# sch.net
KiCad netlist of a schematic drawn in Altium Designer
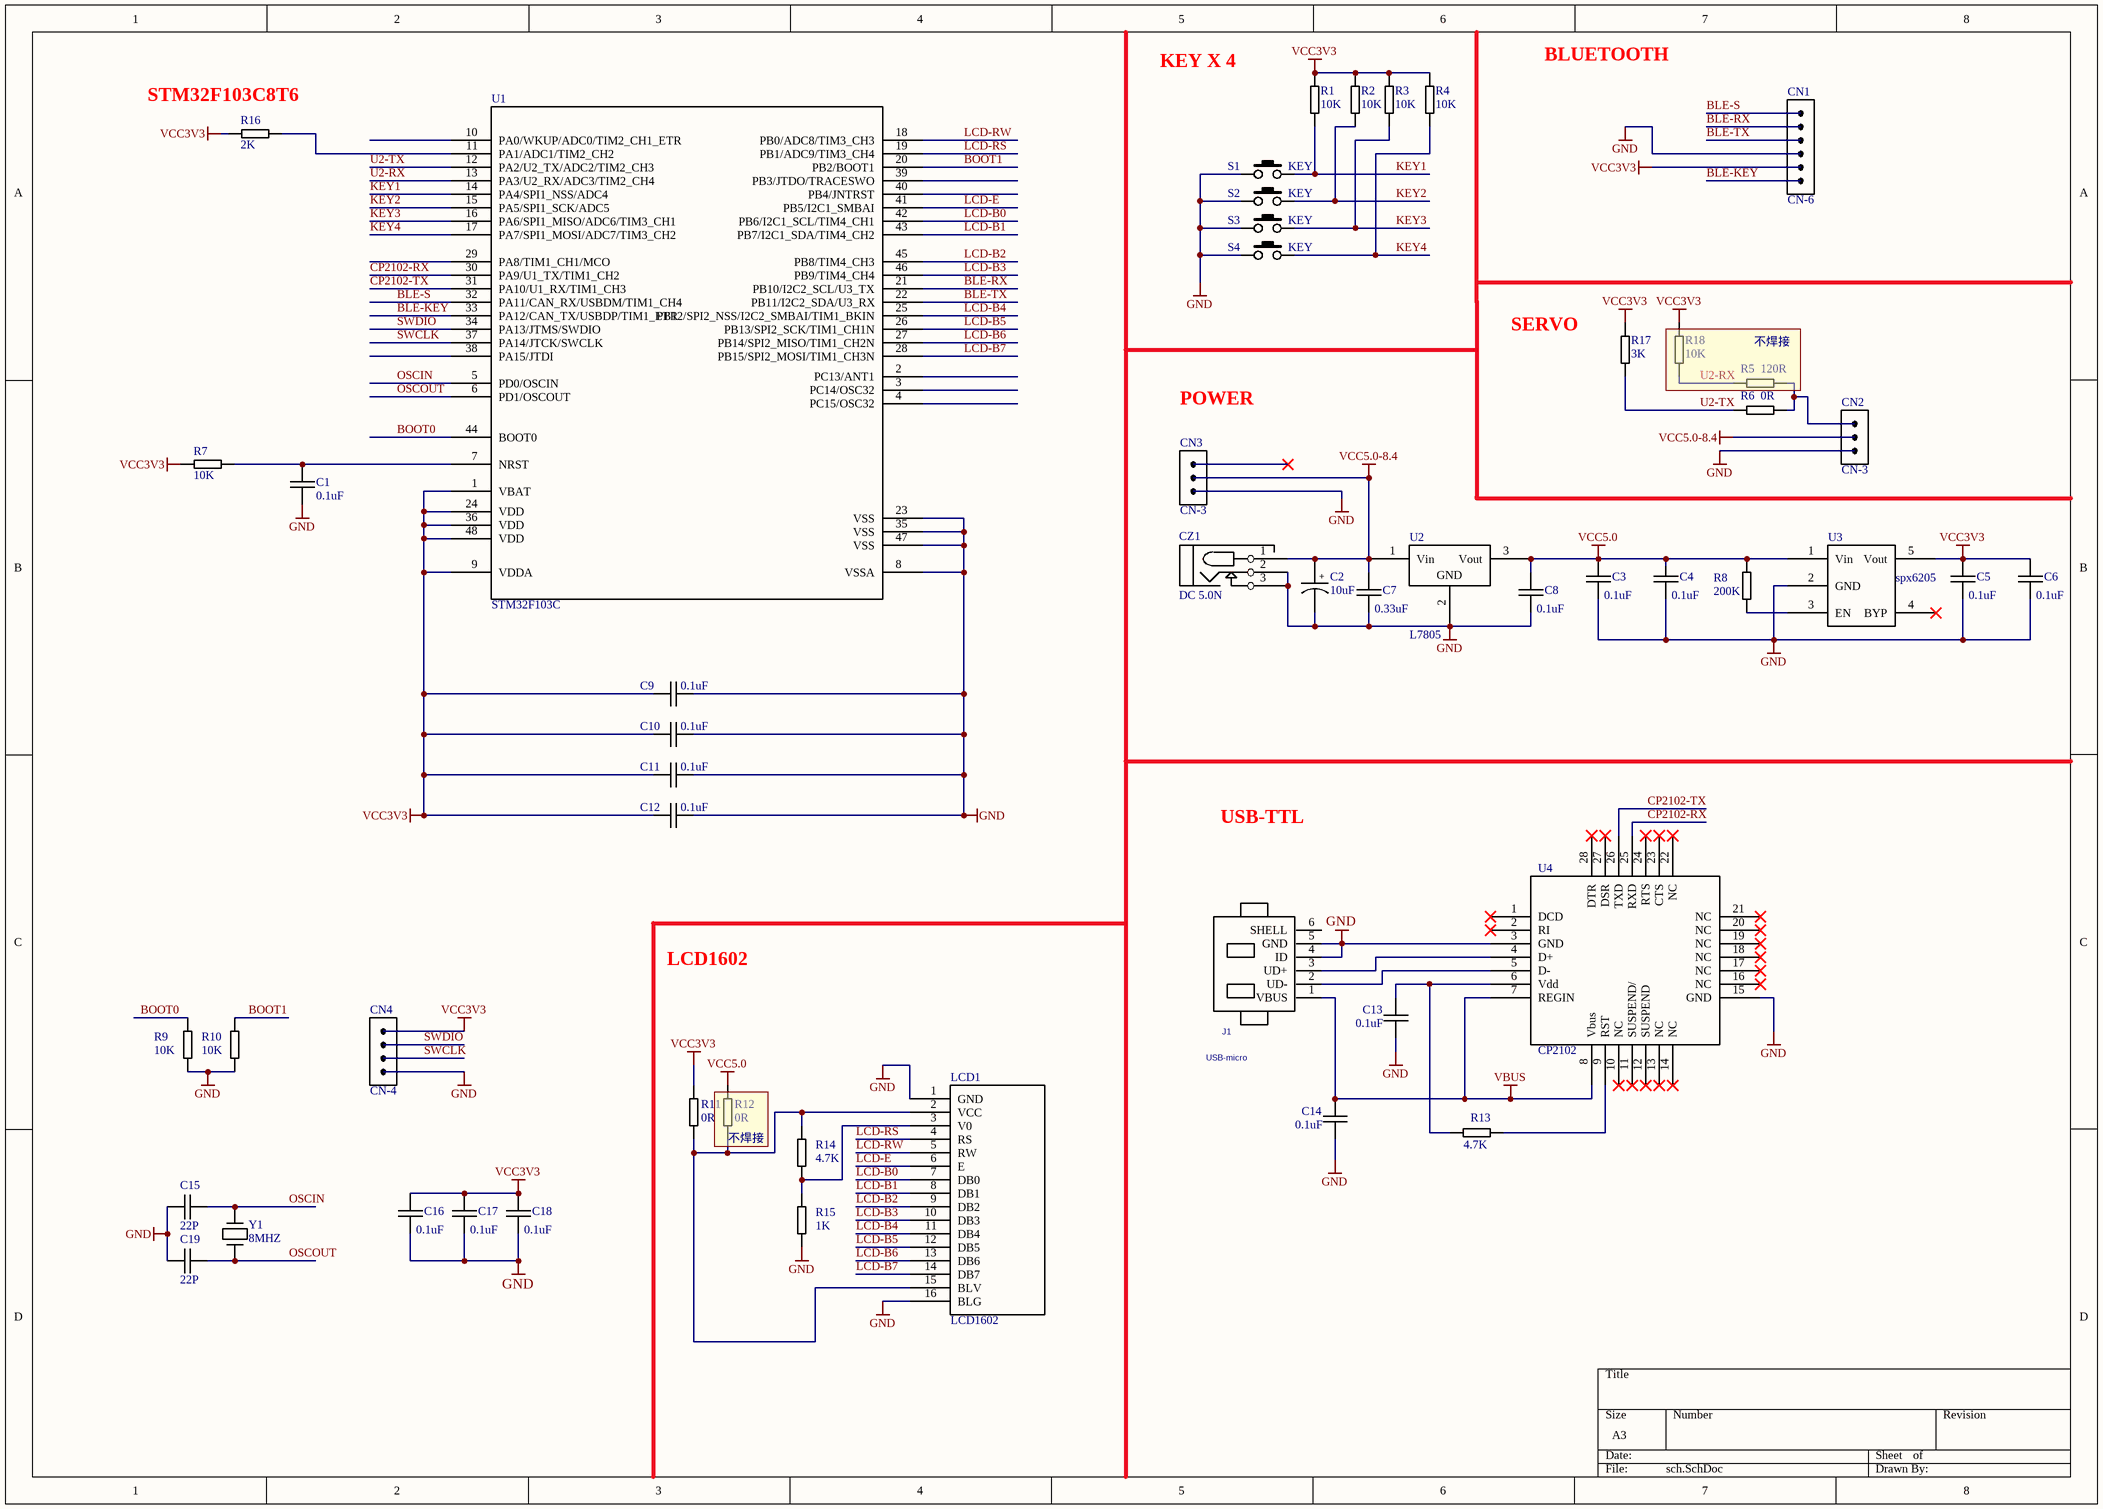
[diagram p0: sch.SchDoc]

(export (version "E")
  (design (tool "Eeschema 10.0.6"))
  (components
    (comp (ref "C1")
      (value "0.1uF")
      (footprint "CAP-0603")
      (description "Capacitor")
      (libsource (lib "综合元件") (part "CAP"))
    )
    (comp (ref "C2")
      (value "10uF")
      (footprint "CAP-A")
      (description "Polar Capacitor")
      (libsource (lib "1-Components") (part "CAP(POL)"))
    )
    (comp (ref "C3")
      (value "0.1uF")
      (footprint "CAP-0603")
      (description "Capacitor")
      (libsource (lib "综合元件") (part "CAP"))
    )
    (comp (ref "C4")
      (value "0.1uF")
      (footprint "CAP-0603")
      (description "Capacitor")
      (libsource (lib "综合元件") (part "CAP"))
    )
    (comp (ref "C5")
      (value "0.1uF")
      (footprint "CAP-0603")
      (description "Capacitor")
      (libsource (lib "综合元件") (part "CAP"))
    )
    (comp (ref "C6")
      (value "0.1uF")
      (footprint "CAP-0603")
      (description "Capacitor")
      (libsource (lib "综合元件") (part "CAP"))
    )
    (comp (ref "C7")
      (value "0.33uF")
      (footprint "CAP-0603")
      (description "Capacitor")
      (libsource (lib "综合元件") (part "CAP"))
    )
    (comp (ref "C8")
      (value "0.1uF")
      (footprint "CAP-0603")
      (description "Capacitor")
      (libsource (lib "综合元件") (part "CAP"))
    )
    (comp (ref "C9")
      (value "0.1uF")
      (footprint "CAP-0603")
      (description "Capacitor")
      (libsource (lib "综合元件") (part "CAP"))
    )
    (comp (ref "C10")
      (value "0.1uF")
      (footprint "CAP-0603")
      (description "Capacitor")
      (libsource (lib "综合元件") (part "CAP"))
    )
    (comp (ref "C11")
      (value "0.1uF")
      (footprint "CAP-0603")
      (description "Capacitor")
      (libsource (lib "综合元件") (part "CAP"))
    )
    (comp (ref "C12")
      (value "0.1uF")
      (footprint "CAP-0603")
      (description "Capacitor")
      (libsource (lib "综合元件") (part "CAP"))
    )
    (comp (ref "C13")
      (value "0.1uF")
      (footprint "CAP-0603")
      (description "Capacitor")
      (libsource (lib "综合元件") (part "CAP"))
    )
    (comp (ref "C14")
      (value "0.1uF")
      (footprint "CAP-0603")
      (description "Capacitor")
      (libsource (lib "综合元件") (part "CAP"))
    )
    (comp (ref "C15")
      (value "22P")
      (footprint "CAP-0603")
      (description "Capacitor")
      (libsource (lib "1-Components") (part "CAP"))
    )
    (comp (ref "C16")
      (value "0.1uF")
      (footprint "CAP-0603")
      (description "Capacitor")
      (libsource (lib "综合元件") (part "CAP"))
    )
    (comp (ref "C17")
      (value "0.1uF")
      (footprint "CAP-0603")
      (description "Capacitor")
      (libsource (lib "综合元件") (part "CAP"))
    )
    (comp (ref "C18")
      (value "0.1uF")
      (footprint "CAP-0603")
      (description "Capacitor")
      (libsource (lib "综合元件") (part "CAP"))
    )
    (comp (ref "C19")
      (value "22P")
      (footprint "CAP-0603")
      (description "Capacitor")
      (libsource (lib "1-Components") (part "CAP"))
    )
    (comp (ref "CN1") (value "CN-6") (footprint "CN-6") (libsource (lib "2-Connectors") (part "CN-6")))
    (comp (ref "CN2") (value "CN-3") (footprint "IDC-3×1") (libsource (lib "2-Connectors") (part "CN-3")))
    (comp (ref "CN3") (value "CN-3") (footprint "IDC-3×1") (libsource (lib "2-Connectors") (part "CN-3")))
    (comp (ref "CN4") (value "CN-4") (footprint "CN-4") (libsource (lib "2-Connectors") (part "CN-4")))
    (comp (ref "CZ1")
      (value "DC 5.0N")
      (footprint "DC-005(N)")
      (libsource (lib "2-Connectors") (part "DC 5.0N"))
    )
    (comp (ref "J1")
      (value "USB-micro")
      (footprint "USB-MICRO")
      (libsource (lib "2-Connectors") (part "USB-micro"))
    )
    (comp (ref "LCD1")
      (value "LCD1602")
      (footprint "LCD1602")
      (libsource (lib "6-Modulars") (part "LCD1602"))
    )
    (comp (ref "R1")
      (value "10K")
      (footprint "RES-0603")
      (description "Resistor")
      (libsource (lib "1-Components") (part "RES"))
    )
    (comp (ref "R2")
      (value "10K")
      (footprint "RES-0603")
      (description "Resistor")
      (libsource (lib "1-Components") (part "RES"))
    )
    (comp (ref "R3")
      (value "10K")
      (footprint "RES-0603")
      (description "Resistor")
      (libsource (lib "1-Components") (part "RES"))
    )
    (comp (ref "R4")
      (value "10K")
      (footprint "RES-0603")
      (description "Resistor")
      (libsource (lib "1-Components") (part "RES"))
    )
    (comp (ref "R5")
      (value "120R")
      (footprint "RES-0603")
      (description "Resistor")
      (libsource (lib "1-Components") (part "RES"))
    )
    (comp (ref "R6")
      (value "0R")
      (footprint "RES-0603")
      (description "Resistor")
      (libsource (lib "1-Components") (part "RES"))
    )
    (comp (ref "R7")
      (value "10K")
      (footprint "RES-0603")
      (description "Resistor")
      (libsource (lib "综合元件") (part "RES"))
    )
    (comp (ref "R8")
      (value "200K")
      (footprint "RES-0603")
      (description "Resistor")
      (libsource (lib "1-Components") (part "RES"))
    )
    (comp (ref "R9")
      (value "10K")
      (footprint "RES-0603")
      (description "Resistor")
      (libsource (lib "1-Components") (part "RES"))
    )
    (comp (ref "R10")
      (value "10K")
      (footprint "RES-0603")
      (description "Resistor")
      (libsource (lib "1-Components") (part "RES"))
    )
    (comp (ref "R11")
      (value "0R")
      (footprint "RES-0603")
      (description "Resistor")
      (libsource (lib "1-Components") (part "RES"))
    )
    (comp (ref "R12")
      (value "0R")
      (footprint "RES-0603")
      (description "Resistor")
      (libsource (lib "1-Components") (part "RES"))
    )
    (comp (ref "R13")
      (value "4.7K")
      (footprint "RES-0603")
      (description "Resistor")
      (libsource (lib "1-Components") (part "RES"))
    )
    (comp (ref "R14")
      (value "4.7K")
      (footprint "RES-0603")
      (description "Resistor")
      (libsource (lib "1-Components") (part "RES"))
    )
    (comp (ref "R15")
      (value "1K")
      (footprint "RES-0603")
      (description "Resistor")
      (libsource (lib "1-Components") (part "RES"))
    )
    (comp (ref "R16")
      (value "2K")
      (footprint "RES-0603")
      (description "Resistor")
      (libsource (lib "1-Components") (part "RES"))
    )
    (comp (ref "R17")
      (value "3K")
      (footprint "RES-0603")
      (description "Resistor")
      (libsource (lib "1-Components") (part "RES"))
    )
    (comp (ref "R18")
      (value "10K")
      (footprint "RES-0603")
      (description "Resistor")
      (libsource (lib "1-Components") (part "RES"))
    )
    (comp (ref "S1") (value "KEY") (footprint "KEY-6A") (libsource (lib "2-Connectors") (part "KEY")))
    (comp (ref "S2") (value "KEY") (footprint "KEY-6A") (libsource (lib "2-Connectors") (part "KEY")))
    (comp (ref "S3") (value "KEY") (footprint "KEY-6A") (libsource (lib "2-Connectors") (part "KEY")))
    (comp (ref "S4") (value "KEY") (footprint "KEY-6A") (libsource (lib "2-Connectors") (part "KEY")))
    (comp (ref "U1")
      (value "STM32F103C")
      (footprint "LQFP-48")
      (fields (field (name "PUBLISHER") "Altium Limited"))
      (libsource (lib "5-ICs Mcu") (part "STM32F103C(LQFP)"))
    )
    (comp (ref "U2") (value "L7805") (footprint "TO-252") (libsource (lib "3-ICs Normal") (part "78XX")))
    (comp (ref "U3")
      (value "spx6205")
      (footprint "SOT-23(5)")
      (libsource (lib "3-ICs Normal") (part "SP6205(FIXED)"))
    )
    (comp (ref "U4") (value "CP2102") (footprint "QFN-28") (libsource (lib "5-ICs Mcu") (part "MPU6050_1")))
    (comp (ref "Y1")
      (value "8MHZ")
      (footprint "XTAL-2512")
      (description "Crystal")
      (libsource (lib "1-Components") (part "XTAL(1)"))
    )
  )
  (nets
    (net (code "1") (name "/BLE-KEY") (class "Default")
      (node (ref "CN1") (pin "6") (pinfunction "6_6") (pintype "passive"))
      (node (ref "U1") (pin "33") (pinfunction "PA12/CAN_TX/USBDP/TIM1_ETR_33") (pintype "passive"))
    )
    (net (code "2") (name "/BLE-RX") (class "Default")
      (node (ref "CN1") (pin "2") (pinfunction "2_2") (pintype "passive"))
      (node (ref "U1") (pin "21") (pinfunction "PB10/I2C2_SCL/U3_TX_21") (pintype "passive"))
    )
    (net (code "3") (name "/BLE-S") (class "Default")
      (node (ref "CN1") (pin "1") (pinfunction "1_1") (pintype "passive"))
      (node (ref "U1") (pin "32") (pinfunction "PA11/CAN_RX/USBDM/TIM1_CH4_32") (pintype "passive"))
    )
    (net (code "4") (name "/BLE-TX") (class "Default")
      (node (ref "CN1") (pin "3") (pinfunction "3_3") (pintype "passive"))
      (node (ref "U1") (pin "22") (pinfunction "PB11/I2C2_SDA/U3_RX_22") (pintype "passive"))
    )
    (net (code "5") (name "/BOOT0") (class "Default")
      (node (ref "R9") (pin "1") (pinfunction "1_1") (pintype "passive"))
      (node (ref "U1") (pin "44") (pinfunction "BOOT0_44") (pintype "passive"))
    )
    (net (code "6") (name "/BOOT1") (class "Default")
      (node (ref "R10") (pin "1") (pinfunction "1_1") (pintype "passive"))
      (node (ref "U1") (pin "20") (pinfunction "PB2/BOOT1_20") (pintype "passive"))
    )
    (net (code "7") (name "/CP2102-RX") (class "Default")
      (node (ref "U1") (pin "30") (pinfunction "PA9/U1_TX/TIM1_CH2_30") (pintype "passive"))
      (node (ref "U4") (pin "25") (pinfunction "RXD_25") (pintype "passive"))
    )
    (net (code "8") (name "/CP2102-TX") (class "Default")
      (node (ref "U1") (pin "31") (pinfunction "PA10/U1_RX/TIM1_CH3_31") (pintype "passive"))
      (node (ref "U4") (pin "26") (pinfunction "TXD_26") (pintype "passive"))
    )
    (net (code "9") (name "/KEY1") (class "Default")
      (node (ref "R1") (pin "1") (pinfunction "1_1") (pintype "passive"))
      (node (ref "S1") (pin "2") (pinfunction "2_2") (pintype "passive"))
      (node (ref "U1") (pin "14") (pinfunction "PA4/SPI1_NSS/ADC4_14") (pintype "passive"))
    )
    (net (code "10") (name "/KEY2") (class "Default")
      (node (ref "R2") (pin "1") (pinfunction "1_1") (pintype "passive"))
      (node (ref "S2") (pin "2") (pinfunction "2_2") (pintype "passive"))
      (node (ref "U1") (pin "15") (pinfunction "PA5/SPI1_SCK/ADC5_15") (pintype "passive"))
    )
    (net (code "11") (name "/KEY3") (class "Default")
      (node (ref "R3") (pin "1") (pinfunction "1_1") (pintype "passive"))
      (node (ref "S3") (pin "2") (pinfunction "2_2") (pintype "passive"))
      (node (ref "U1") (pin "16") (pinfunction "PA6/SPI1_MISO/ADC6/TIM3_CH1_16") (pintype "passive"))
    )
    (net (code "12") (name "/KEY4") (class "Default")
      (node (ref "R4") (pin "1") (pinfunction "1_1") (pintype "passive"))
      (node (ref "S4") (pin "2") (pinfunction "2_2") (pintype "passive"))
      (node (ref "U1") (pin "17") (pinfunction "PA7/SPI1_MOSI/ADC7/TIM3_CH2_17") (pintype "passive"))
    )
    (net (code "13") (name "/LCD-B0") (class "Default")
      (node (ref "LCD1") (pin "7") (pinfunction "DB0_7") (pintype "passive"))
      (node (ref "U1") (pin "42") (pinfunction "PB6/I2C1_SCL/TIM4_CH1_42") (pintype "passive"))
    )
    (net (code "14") (name "/LCD-B1") (class "Default")
      (node (ref "LCD1") (pin "8") (pinfunction "DB1_8") (pintype "passive"))
      (node (ref "U1") (pin "43") (pinfunction "PB7/I2C1_SDA/TIM4_CH2_43") (pintype "passive"))
    )
    (net (code "15") (name "/LCD-B2") (class "Default")
      (node (ref "LCD1") (pin "9") (pinfunction "DB2_9") (pintype "passive"))
      (node (ref "U1") (pin "45") (pinfunction "PB8/TIM4_CH3_45") (pintype "passive"))
    )
    (net (code "16") (name "/LCD-B3") (class "Default")
      (node (ref "LCD1") (pin "10") (pinfunction "DB3_10") (pintype "passive"))
      (node (ref "U1") (pin "46") (pinfunction "PB9/TIM4_CH4_46") (pintype "passive"))
    )
    (net (code "17") (name "/LCD-B4") (class "Default")
      (node (ref "LCD1") (pin "11") (pinfunction "DB4_11") (pintype "passive"))
      (node (ref "U1") (pin "25") (pinfunction "PB12/SPI2_NSS/I2C2_SMBAI/TIM1_BKIN_25") (pintype "passive"))
    )
    (net (code "18") (name "/LCD-B5") (class "Default")
      (node (ref "LCD1") (pin "12") (pinfunction "DB5_12") (pintype "passive"))
      (node (ref "U1") (pin "26") (pinfunction "PB13/SPI2_SCK/TIM1_CH1N_26") (pintype "passive"))
    )
    (net (code "19") (name "/LCD-B6") (class "Default")
      (node (ref "LCD1") (pin "13") (pinfunction "DB6_13") (pintype "passive"))
      (node (ref "U1") (pin "27") (pinfunction "PB14/SPI2_MISO/TIM1_CH2N_27") (pintype "passive"))
    )
    (net (code "20") (name "/LCD-B7") (class "Default")
      (node (ref "LCD1") (pin "14") (pinfunction "DB7_14") (pintype "passive"))
      (node (ref "U1") (pin "28") (pinfunction "PB15/SPI2_MOSI/TIM1_CH3N_28") (pintype "passive"))
    )
    (net (code "21") (name "/LCD-E") (class "Default")
      (node (ref "LCD1") (pin "6") (pinfunction "E_6") (pintype "passive"))
      (node (ref "U1") (pin "41") (pinfunction "PB5/I2C1_SMBAI_41") (pintype "passive"))
    )
    (net (code "22") (name "/LCD-RS") (class "Default")
      (node (ref "LCD1") (pin "4") (pinfunction "RS_4") (pintype "passive"))
      (node (ref "U1") (pin "19") (pinfunction "PB1/ADC9/TIM3_CH4_19") (pintype "passive"))
    )
    (net (code "23") (name "/LCD-RW") (class "Default")
      (node (ref "LCD1") (pin "5") (pinfunction "RW_5") (pintype "passive"))
      (node (ref "U1") (pin "18") (pinfunction "PB0/ADC8/TIM3_CH3_18") (pintype "passive"))
    )
    (net (code "24") (name "/OSCIN") (class "Default")
      (node (ref "C15") (pin "2") (pinfunction "2_2") (pintype "passive"))
      (node (ref "U1") (pin "5") (pinfunction "PD0/OSCIN_5") (pintype "passive"))
      (node (ref "Y1") (pin "2") (pinfunction "2_2") (pintype "passive"))
    )
    (net (code "25") (name "/OSCOUT") (class "Default")
      (node (ref "C19") (pin "2") (pinfunction "2_2") (pintype "passive"))
      (node (ref "U1") (pin "6") (pinfunction "PD1/OSCOUT_6") (pintype "passive"))
      (node (ref "Y1") (pin "1") (pinfunction "1_1") (pintype "passive"))
    )
    (net (code "26") (name "/SWCLK") (class "Default")
      (node (ref "CN4") (pin "3") (pinfunction "3_3") (pintype "passive"))
      (node (ref "U1") (pin "37") (pinfunction "PA14/JTCK/SWCLK_37") (pintype "passive"))
    )
    (net (code "27") (name "/SWDIO") (class "Default")
      (node (ref "CN4") (pin "2") (pinfunction "2_2") (pintype "passive"))
      (node (ref "U1") (pin "34") (pinfunction "PA13/JTMS/SWDIO_34") (pintype "passive"))
    )
    (net (code "28") (name "/U2-RX") (class "Default")
      (node (ref "R18") (pin "1") (pinfunction "1_1") (pintype "passive"))
      (node (ref "R5") (pin "1") (pinfunction "1_1") (pintype "passive"))
      (node (ref "U1") (pin "13") (pinfunction "PA3/U2_RX/ADC3/TIM2_CH4_13") (pintype "passive"))
    )
    (net (code "29") (name "/U2-TX") (class "Default")
      (node (ref "R17") (pin "1") (pinfunction "1_1") (pintype "passive"))
      (node (ref "R6") (pin "1") (pinfunction "1_1") (pintype "passive"))
      (node (ref "U1") (pin "12") (pinfunction "PA2/U2_TX/ADC2/TIM2_CH3_12") (pintype "passive"))
    )
    (net (code "30") (name "GND") (class "Default")
      (node (ref "C1") (pin "2") (pinfunction "2_2") (pintype "passive"))
      (node (ref "C10") (pin "1") (pinfunction "1_1") (pintype "passive"))
      (node (ref "C11") (pin "1") (pinfunction "1_1") (pintype "passive"))
      (node (ref "C12") (pin "1") (pinfunction "1_1") (pintype "passive"))
      (node (ref "C13") (pin "2") (pinfunction "2_2") (pintype "passive"))
      (node (ref "C14") (pin "2") (pinfunction "2_2") (pintype "passive"))
      (node (ref "C15") (pin "1") (pinfunction "1_1") (pintype "passive"))
      (node (ref "C16") (pin "2") (pinfunction "2_2") (pintype "passive"))
      (node (ref "C17") (pin "2") (pinfunction "2_2") (pintype "passive"))
      (node (ref "C18") (pin "2") (pinfunction "2_2") (pintype "passive"))
      (node (ref "C19") (pin "1") (pinfunction "1_1") (pintype "passive"))
      (node (ref "C2") (pin "2") (pinfunction "2_2") (pintype "passive"))
      (node (ref "C3") (pin "2") (pinfunction "2_2") (pintype "passive"))
      (node (ref "C4") (pin "2") (pinfunction "2_2") (pintype "passive"))
      (node (ref "C5") (pin "2") (pinfunction "2_2") (pintype "passive"))
      (node (ref "C6") (pin "2") (pinfunction "2_2") (pintype "passive"))
      (node (ref "C7") (pin "2") (pinfunction "2_2") (pintype "passive"))
      (node (ref "C8") (pin "2") (pinfunction "2_2") (pintype "passive"))
      (node (ref "C9") (pin "1") (pinfunction "1_1") (pintype "passive"))
      (node (ref "CN1") (pin "4") (pinfunction "4_4") (pintype "passive"))
      (node (ref "CN2") (pin "3") (pinfunction "3_3") (pintype "passive"))
      (node (ref "CN3") (pin "3") (pinfunction "3_3") (pintype "passive"))
      (node (ref "CN4") (pin "4") (pinfunction "4_4") (pintype "passive"))
      (node (ref "CZ1") (pin "2") (pinfunction "A_2") (pintype "passive"))
      (node (ref "CZ1") (pin "3") (pinfunction "B_3") (pintype "passive"))
      (node (ref "J1") (pin "4") (pinfunction "ID_4") (pintype "passive"))
      (node (ref "J1") (pin "5") (pinfunction "GND_5") (pintype "passive"))
      (node (ref "LCD1") (pin "1") (pinfunction "GND_1") (pintype "passive"))
      (node (ref "LCD1") (pin "16") (pinfunction "BLG_16") (pintype "passive"))
      (node (ref "R10") (pin "2") (pinfunction "2_2") (pintype "passive"))
      (node (ref "R15") (pin "1") (pinfunction "1_1") (pintype "passive"))
      (node (ref "R9") (pin "2") (pinfunction "2_2") (pintype "passive"))
      (node (ref "S1") (pin "1") (pinfunction "1_1") (pintype "passive"))
      (node (ref "S2") (pin "1") (pinfunction "1_1") (pintype "passive"))
      (node (ref "S3") (pin "1") (pinfunction "1_1") (pintype "passive"))
      (node (ref "S4") (pin "1") (pinfunction "1_1") (pintype "passive"))
      (node (ref "U1") (pin "23") (pinfunction "VSS_23") (pintype "passive"))
      (node (ref "U1") (pin "35") (pinfunction "VSS_35") (pintype "passive"))
      (node (ref "U1") (pin "47") (pinfunction "VSS_47") (pintype "passive"))
      (node (ref "U1") (pin "8") (pinfunction "VSSA_8") (pintype "passive"))
      (node (ref "U2") (pin "2") (pinfunction "GND_2") (pintype "passive"))
      (node (ref "U3") (pin "2") (pinfunction "GND_2") (pintype "passive"))
      (node (ref "U4") (pin "15") (pinfunction "GND_15") (pintype "passive"))
      (node (ref "U4") (pin "3") (pinfunction "GND_3") (pintype "passive"))
    )
    (net (code "31") (name "Net-(CN2-Pad1)") (class "Default")
      (node (ref "CN2") (pin "1") (pinfunction "1_1") (pintype "passive"))
      (node (ref "R5") (pin "2") (pinfunction "2_2") (pintype "passive"))
      (node (ref "R6") (pin "2") (pinfunction "2_2") (pintype "passive"))
    )
    (net (code "32") (name "Net-(J1-UD+)") (class "Default")
      (node (ref "J1") (pin "3") (pinfunction "UD+_3") (pintype "passive"))
      (node (ref "U4") (pin "4") (pinfunction "D+_4") (pintype "passive"))
    )
    (net (code "33") (name "Net-(J1-UD-)") (class "Default")
      (node (ref "J1") (pin "2") (pinfunction "UD-_2") (pintype "passive"))
      (node (ref "U4") (pin "5") (pinfunction "D-_5") (pintype "passive"))
    )
    (net (code "34") (name "Net-(LCD1-BLV)") (class "Default")
      (node (ref "LCD1") (pin "15") (pinfunction "BLV_15") (pintype "passive"))
      (node (ref "LCD1") (pin "2") (pinfunction "VCC_2") (pintype "passive"))
      (node (ref "R11") (pin "1") (pinfunction "1_1") (pintype "passive"))
      (node (ref "R12") (pin "1") (pinfunction "1_1") (pintype "passive"))
      (node (ref "R14") (pin "2") (pinfunction "2_2") (pintype "passive"))
    )
    (net (code "35") (name "Net-(LCD1-V0)") (class "Default")
      (node (ref "LCD1") (pin "3") (pinfunction "V0_3") (pintype "passive"))
      (node (ref "R14") (pin "1") (pinfunction "1_1") (pintype "passive"))
      (node (ref "R15") (pin "2") (pinfunction "2_2") (pintype "passive"))
    )
    (net (code "36") (name "Net-(U1-NRST)") (class "Default")
      (node (ref "C1") (pin "1") (pinfunction "1_1") (pintype "passive"))
      (node (ref "R7") (pin "2") (pinfunction "2_2") (pintype "passive"))
      (node (ref "U1") (pin "7") (pinfunction "NRST_7") (pintype "passive"))
    )
    (net (code "37") (name "Net-(U1-PA1{slash}ADC1{slash}TIM2_CH2)") (class "Default")
      (node (ref "R16") (pin "1") (pinfunction "1_1") (pintype "passive"))
      (node (ref "U1") (pin "11") (pinfunction "PA1/ADC1/TIM2_CH2_11") (pintype "passive"))
    )
    (net (code "38") (name "Net-(U3-EN)") (class "Default")
      (node (ref "R8") (pin "2") (pinfunction "2_2") (pintype "passive"))
      (node (ref "U3") (pin "3") (pinfunction "EN_3") (pintype "passive"))
    )
    (net (code "39") (name "Net-(U4-RST)") (class "Default")
      (node (ref "R13") (pin "2") (pinfunction "2_2") (pintype "passive"))
      (node (ref "U4") (pin "9") (pinfunction "RST_9") (pintype "passive"))
    )
    (net (code "40") (name "Net-(U4-Vdd)") (class "Default")
      (node (ref "C13") (pin "1") (pinfunction "1_1") (pintype "passive"))
      (node (ref "R13") (pin "1") (pinfunction "1_1") (pintype "passive"))
      (node (ref "U4") (pin "6") (pinfunction "Vdd_6") (pintype "passive"))
    )
    (net (code "41") (name "VBUS") (class "Default")
      (node (ref "C14") (pin "1") (pinfunction "1_1") (pintype "passive"))
      (node (ref "J1") (pin "1") (pinfunction "VBUS_1") (pintype "passive"))
      (node (ref "U4") (pin "7") (pinfunction "REGIN_7") (pintype "passive"))
      (node (ref "U4") (pin "8") (pinfunction "Vbus_8") (pintype "passive"))
    )
    (net (code "42") (name "VCC3V3") (class "Default")
      (node (ref "C10") (pin "2") (pinfunction "2_2") (pintype "passive"))
      (node (ref "C11") (pin "2") (pinfunction "2_2") (pintype "passive"))
      (node (ref "C12") (pin "2") (pinfunction "2_2") (pintype "passive"))
      (node (ref "C16") (pin "1") (pinfunction "1_1") (pintype "passive"))
      (node (ref "C17") (pin "1") (pinfunction "1_1") (pintype "passive"))
      (node (ref "C18") (pin "1") (pinfunction "1_1") (pintype "passive"))
      (node (ref "C5") (pin "1") (pinfunction "1_1") (pintype "passive"))
      (node (ref "C6") (pin "1") (pinfunction "1_1") (pintype "passive"))
      (node (ref "C9") (pin "2") (pinfunction "2_2") (pintype "passive"))
      (node (ref "CN1") (pin "5") (pinfunction "5_5") (pintype "passive"))
      (node (ref "CN4") (pin "1") (pinfunction "1_1") (pintype "passive"))
      (node (ref "R1") (pin "2") (pinfunction "2_2") (pintype "passive"))
      (node (ref "R11") (pin "2") (pinfunction "2_2") (pintype "passive"))
      (node (ref "R16") (pin "2") (pinfunction "2_2") (pintype "passive"))
      (node (ref "R17") (pin "2") (pinfunction "2_2") (pintype "passive"))
      (node (ref "R18") (pin "2") (pinfunction "2_2") (pintype "passive"))
      (node (ref "R2") (pin "2") (pinfunction "2_2") (pintype "passive"))
      (node (ref "R3") (pin "2") (pinfunction "2_2") (pintype "passive"))
      (node (ref "R4") (pin "2") (pinfunction "2_2") (pintype "passive"))
      (node (ref "R7") (pin "1") (pinfunction "1_1") (pintype "passive"))
      (node (ref "U1") (pin "1") (pinfunction "VBAT_1") (pintype "passive"))
      (node (ref "U1") (pin "24") (pinfunction "VDD_24") (pintype "passive"))
      (node (ref "U1") (pin "36") (pinfunction "VDD_36") (pintype "passive"))
      (node (ref "U1") (pin "48") (pinfunction "VDD_48") (pintype "passive"))
      (node (ref "U1") (pin "9") (pinfunction "VDDA_9") (pintype "passive"))
      (node (ref "U3") (pin "5") (pinfunction "Vout_5") (pintype "passive"))
    )
    (net (code "43") (name "VCC5.0") (class "Default")
      (node (ref "C3") (pin "1") (pinfunction "1_1") (pintype "passive"))
      (node (ref "C4") (pin "1") (pinfunction "1_1") (pintype "passive"))
      (node (ref "C8") (pin "1") (pinfunction "1_1") (pintype "passive"))
      (node (ref "R12") (pin "2") (pinfunction "2_2") (pintype "passive"))
      (node (ref "R8") (pin "1") (pinfunction "1_1") (pintype "passive"))
      (node (ref "U2") (pin "3") (pinfunction "Vout_3") (pintype "passive"))
      (node (ref "U3") (pin "1") (pinfunction "Vin_1") (pintype "passive"))
    )
    (net (code "44") (name "VCC5.0-8.4") (class "Default")
      (node (ref "C2") (pin "1") (pinfunction "1_1") (pintype "passive"))
      (node (ref "C7") (pin "1") (pinfunction "1_1") (pintype "passive"))
      (node (ref "CN2") (pin "2") (pinfunction "2_2") (pintype "passive"))
      (node (ref "CN3") (pin "2") (pinfunction "2_2") (pintype "passive"))
      (node (ref "CZ1") (pin "1") (pinfunction "+_1") (pintype "passive"))
      (node (ref "U2") (pin "1") (pinfunction "Vin_1") (pintype "passive"))
    )
    (net (code "45") (name "unconnected-(CN3-Pad1)") (class "Default")
      (node (ref "CN3") (pin "1") (pinfunction "1_1") (pintype "passive+no_connect"))
    )
    (net (code "46") (name "unconnected-(J1-SHELL-Pad6)") (class "Default")
      (node (ref "J1") (pin "6") (pinfunction "SHELL_6") (pintype "passive"))
    )
    (net (code "47") (name "unconnected-(U1-PA0{slash}WKUP{slash}ADC0{slash}TIM2_CH1_ETR-Pad10)") (class "Default")
      (node (ref "U1") (pin "10") (pinfunction "PA0/WKUP/ADC0/TIM2_CH1_ETR_10") (pintype "passive"))
    )
    (net (code "48") (name "unconnected-(U1-PA8{slash}TIM1_CH1{slash}MCO-Pad29)") (class "Default")
      (node (ref "U1") (pin "29") (pinfunction "PA8/TIM1_CH1/MCO_29") (pintype "passive"))
    )
    (net (code "49") (name "unconnected-(U1-PA15{slash}JTDI-Pad38)") (class "Default")
      (node (ref "U1") (pin "38") (pinfunction "PA15/JTDI_38") (pintype "passive"))
    )
    (net (code "50") (name "unconnected-(U1-PB3{slash}JTDO{slash}TRACESWO-Pad39)") (class "Default")
      (node (ref "U1") (pin "39") (pinfunction "PB3/JTDO/TRACESWO_39") (pintype "passive"))
    )
    (net (code "51") (name "unconnected-(U1-PB4{slash}JNTRST-Pad40)") (class "Default")
      (node (ref "U1") (pin "40") (pinfunction "PB4/JNTRST_40") (pintype "passive"))
    )
    (net (code "52") (name "unconnected-(U1-PC13{slash}ANT1-Pad2)") (class "Default")
      (node (ref "U1") (pin "2") (pinfunction "PC13/ANT1_2") (pintype "passive"))
    )
    (net (code "53") (name "unconnected-(U1-PC14{slash}OSC32-Pad3)") (class "Default")
      (node (ref "U1") (pin "3") (pinfunction "PC14/OSC32_3") (pintype "passive"))
    )
    (net (code "54") (name "unconnected-(U1-PC15{slash}OSC32-Pad4)") (class "Default")
      (node (ref "U1") (pin "4") (pinfunction "PC15/OSC32_4") (pintype "passive"))
    )
    (net (code "55") (name "unconnected-(U3-BYP-Pad4)") (class "Default")
      (node (ref "U3") (pin "4") (pinfunction "BYP_4") (pintype "passive+no_connect"))
    )
    (net (code "56") (name "unconnected-(U4-CTS-Pad23)") (class "Default")
      (node (ref "U4") (pin "23") (pinfunction "CTS_23") (pintype "passive+no_connect"))
    )
    (net (code "57") (name "unconnected-(U4-DCD-Pad1)") (class "Default")
      (node (ref "U4") (pin "1") (pinfunction "DCD_1") (pintype "passive+no_connect"))
    )
    (net (code "58") (name "unconnected-(U4-DSR-Pad27)") (class "Default")
      (node (ref "U4") (pin "27") (pinfunction "DSR_27") (pintype "passive+no_connect"))
    )
    (net (code "59") (name "unconnected-(U4-DTR-Pad28)") (class "Default")
      (node (ref "U4") (pin "28") (pinfunction "DTR_28") (pintype "passive+no_connect"))
    )
    (net (code "60") (name "unconnected-(U4-NC-Pad10)") (class "Default")
      (node (ref "U4") (pin "10") (pinfunction "NC_10") (pintype "passive+no_connect"))
    )
    (net (code "61") (name "unconnected-(U4-NC-Pad13)") (class "Default")
      (node (ref "U4") (pin "13") (pinfunction "NC_13") (pintype "passive+no_connect"))
    )
    (net (code "62") (name "unconnected-(U4-NC-Pad14)") (class "Default")
      (node (ref "U4") (pin "14") (pinfunction "NC_14") (pintype "passive+no_connect"))
    )
    (net (code "63") (name "unconnected-(U4-NC-Pad16)") (class "Default")
      (node (ref "U4") (pin "16") (pinfunction "NC_16") (pintype "passive+no_connect"))
    )
    (net (code "64") (name "unconnected-(U4-NC-Pad17)") (class "Default")
      (node (ref "U4") (pin "17") (pinfunction "NC_17") (pintype "passive+no_connect"))
    )
    (net (code "65") (name "unconnected-(U4-NC-Pad18)") (class "Default")
      (node (ref "U4") (pin "18") (pinfunction "NC_18") (pintype "passive+no_connect"))
    )
    (net (code "66") (name "unconnected-(U4-NC-Pad19)") (class "Default")
      (node (ref "U4") (pin "19") (pinfunction "NC_19") (pintype "passive+no_connect"))
    )
    (net (code "67") (name "unconnected-(U4-NC-Pad20)") (class "Default")
      (node (ref "U4") (pin "20") (pinfunction "NC_20") (pintype "passive+no_connect"))
    )
    (net (code "68") (name "unconnected-(U4-NC-Pad21)") (class "Default")
      (node (ref "U4") (pin "21") (pinfunction "NC_21") (pintype "passive+no_connect"))
    )
    (net (code "69") (name "unconnected-(U4-NC-Pad22)") (class "Default")
      (node (ref "U4") (pin "22") (pinfunction "NC_22") (pintype "passive+no_connect"))
    )
    (net (code "70") (name "unconnected-(U4-RI-Pad2)") (class "Default")
      (node (ref "U4") (pin "2") (pinfunction "RI_2") (pintype "passive+no_connect"))
    )
    (net (code "71") (name "unconnected-(U4-RTS-Pad24)") (class "Default")
      (node (ref "U4") (pin "24") (pinfunction "RTS_24") (pintype "passive+no_connect"))
    )
    (net (code "72") (name "unconnected-(U4-SUSPEND-Pad12)") (class "Default")
      (node (ref "U4") (pin "12") (pinfunction "SUSPEND_12") (pintype "passive+no_connect"))
    )
    (net (code "73") (name "unconnected-(U4-SUSPEND{slash}-Pad11)") (class "Default")
      (node (ref "U4") (pin "11") (pinfunction "SUSPEND/_11") (pintype "passive+no_connect"))
    )
  )
)
